# Sheet1_35131-35133.net
KiCad netlist of a schematic drawn in Altium Designer
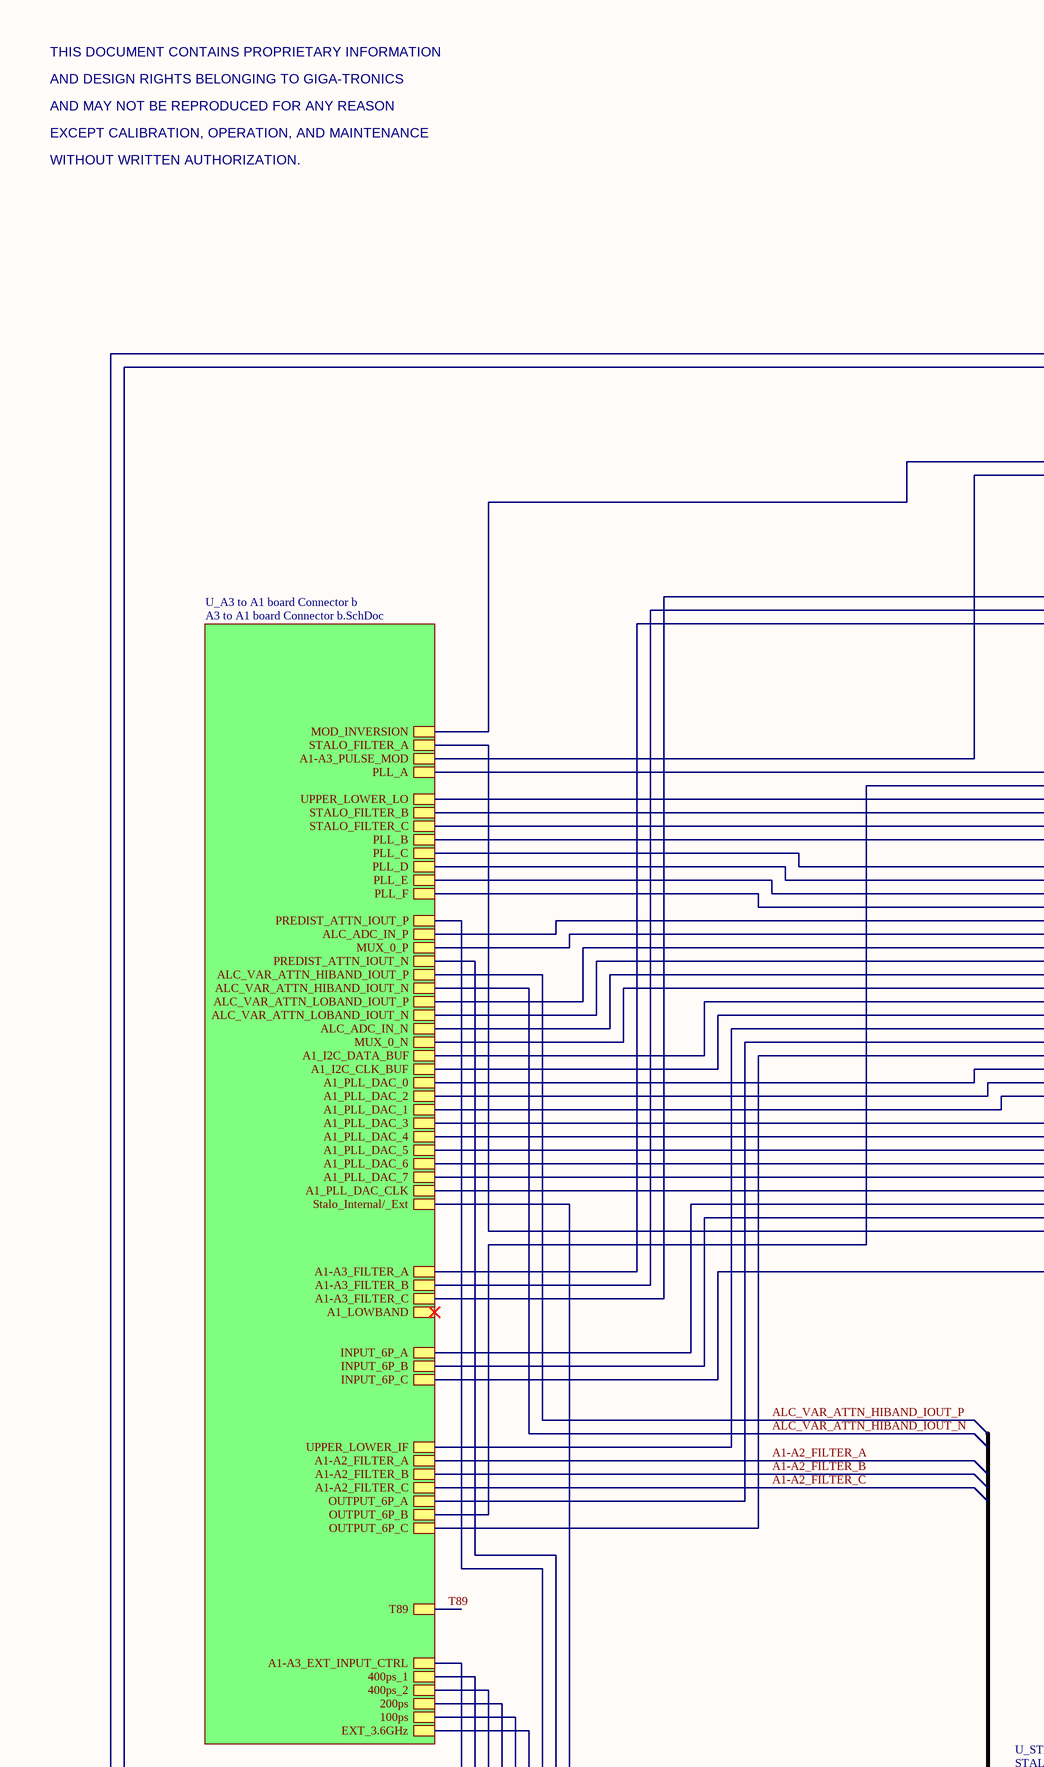
[diagram p0: Sheet1_35131-35133.SchDoc, top left]
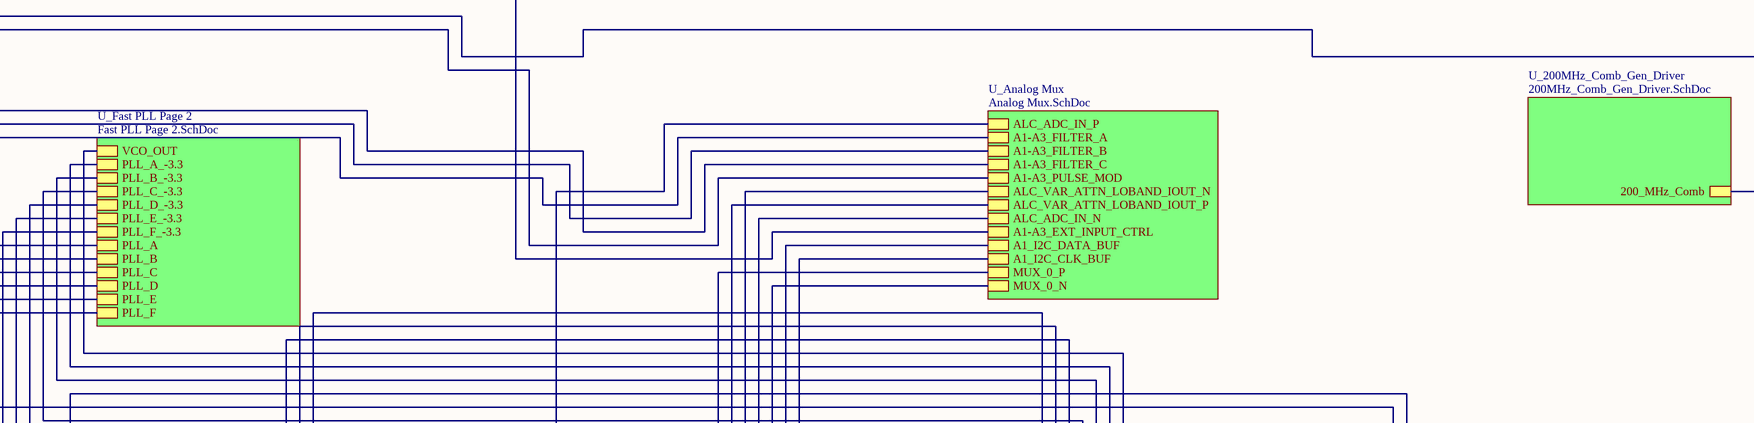
[diagram p1: Sheet1_35131-35133.SchDoc, top middle]
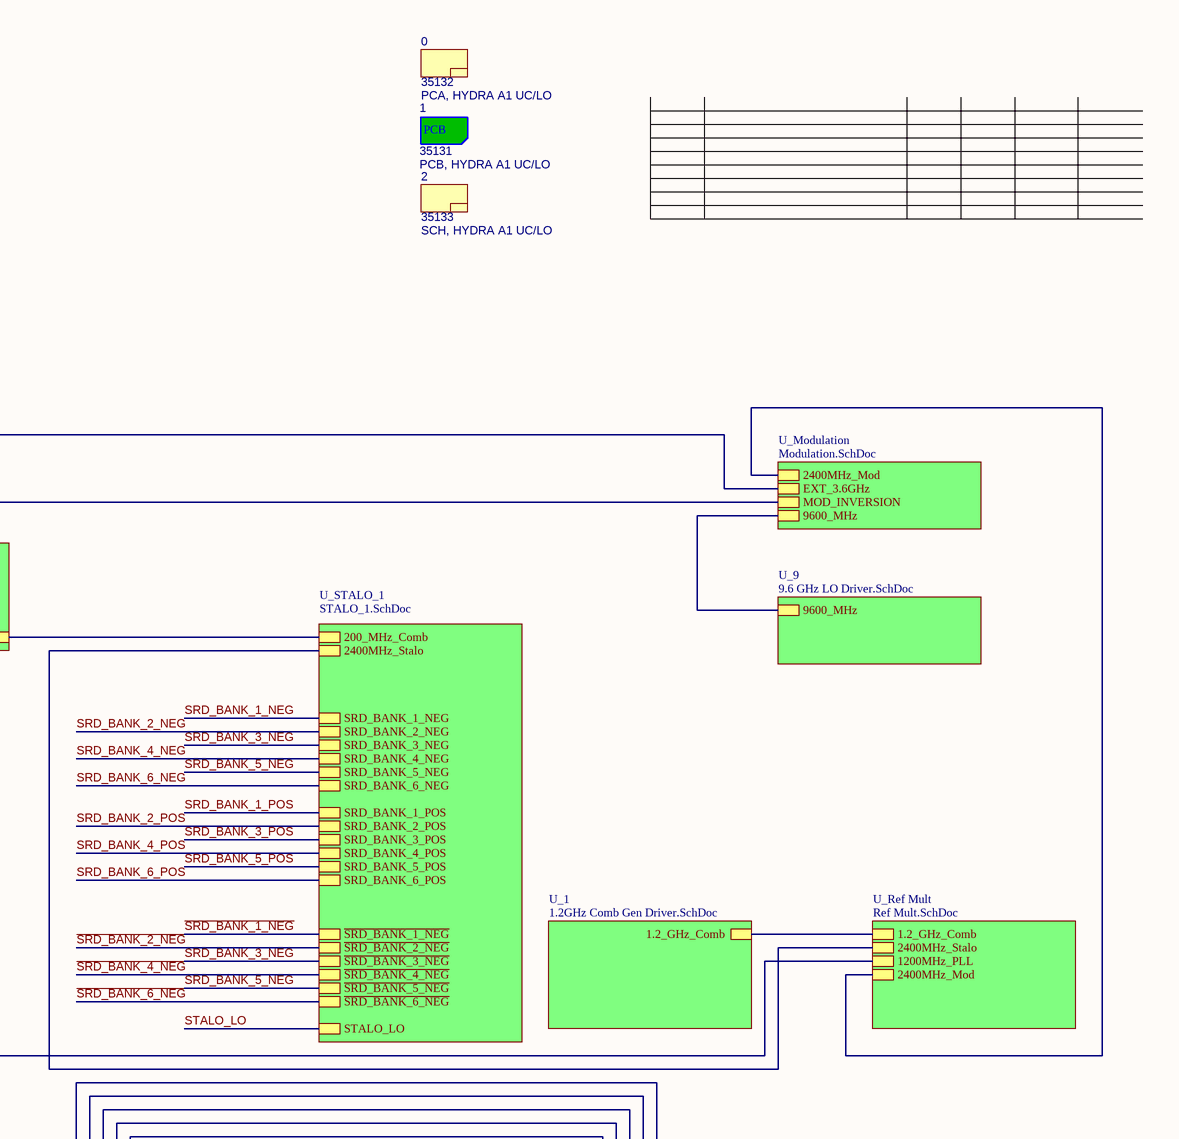
[diagram p2: Sheet1_35131-35133.SchDoc, top right]
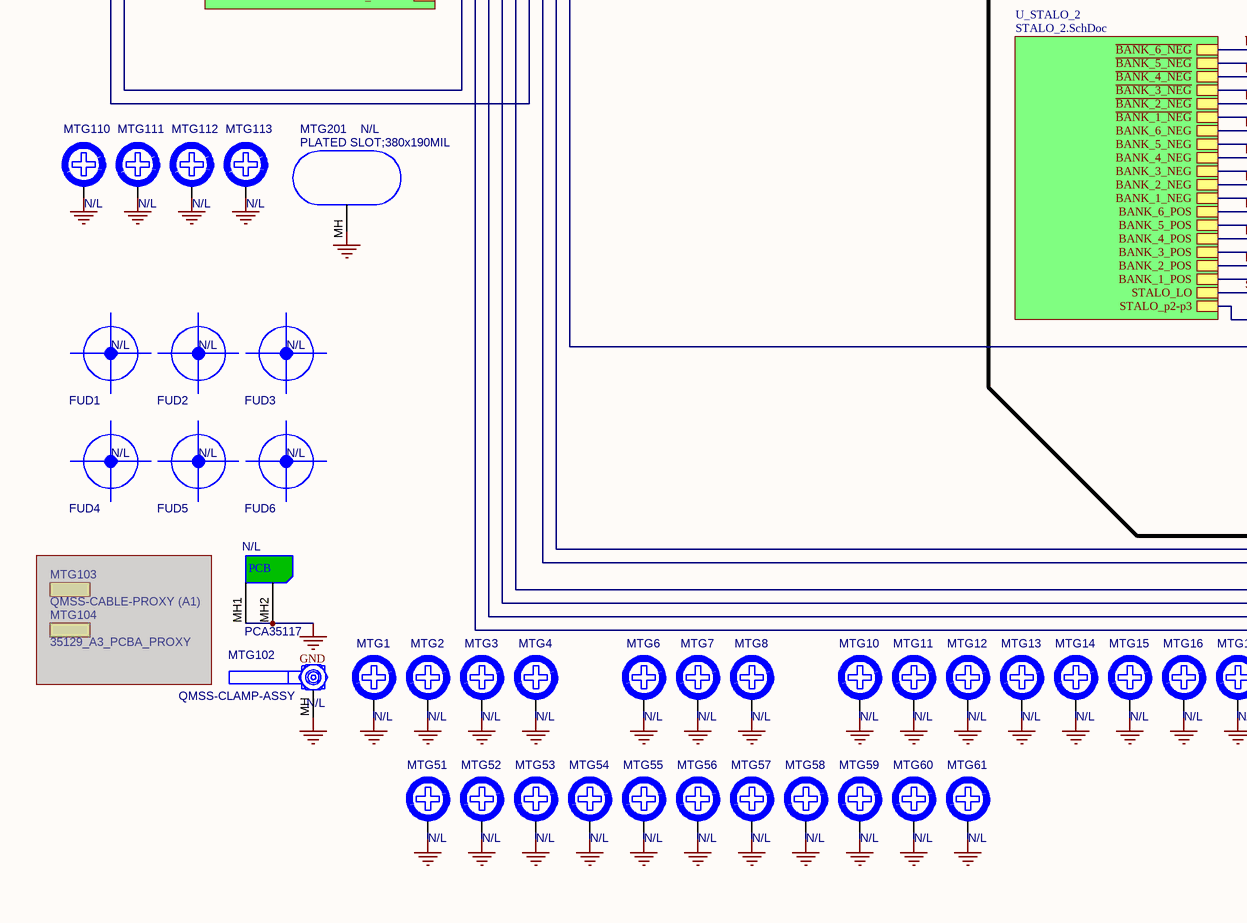
[diagram p3: Sheet1_35131-35133.SchDoc, bottom left]
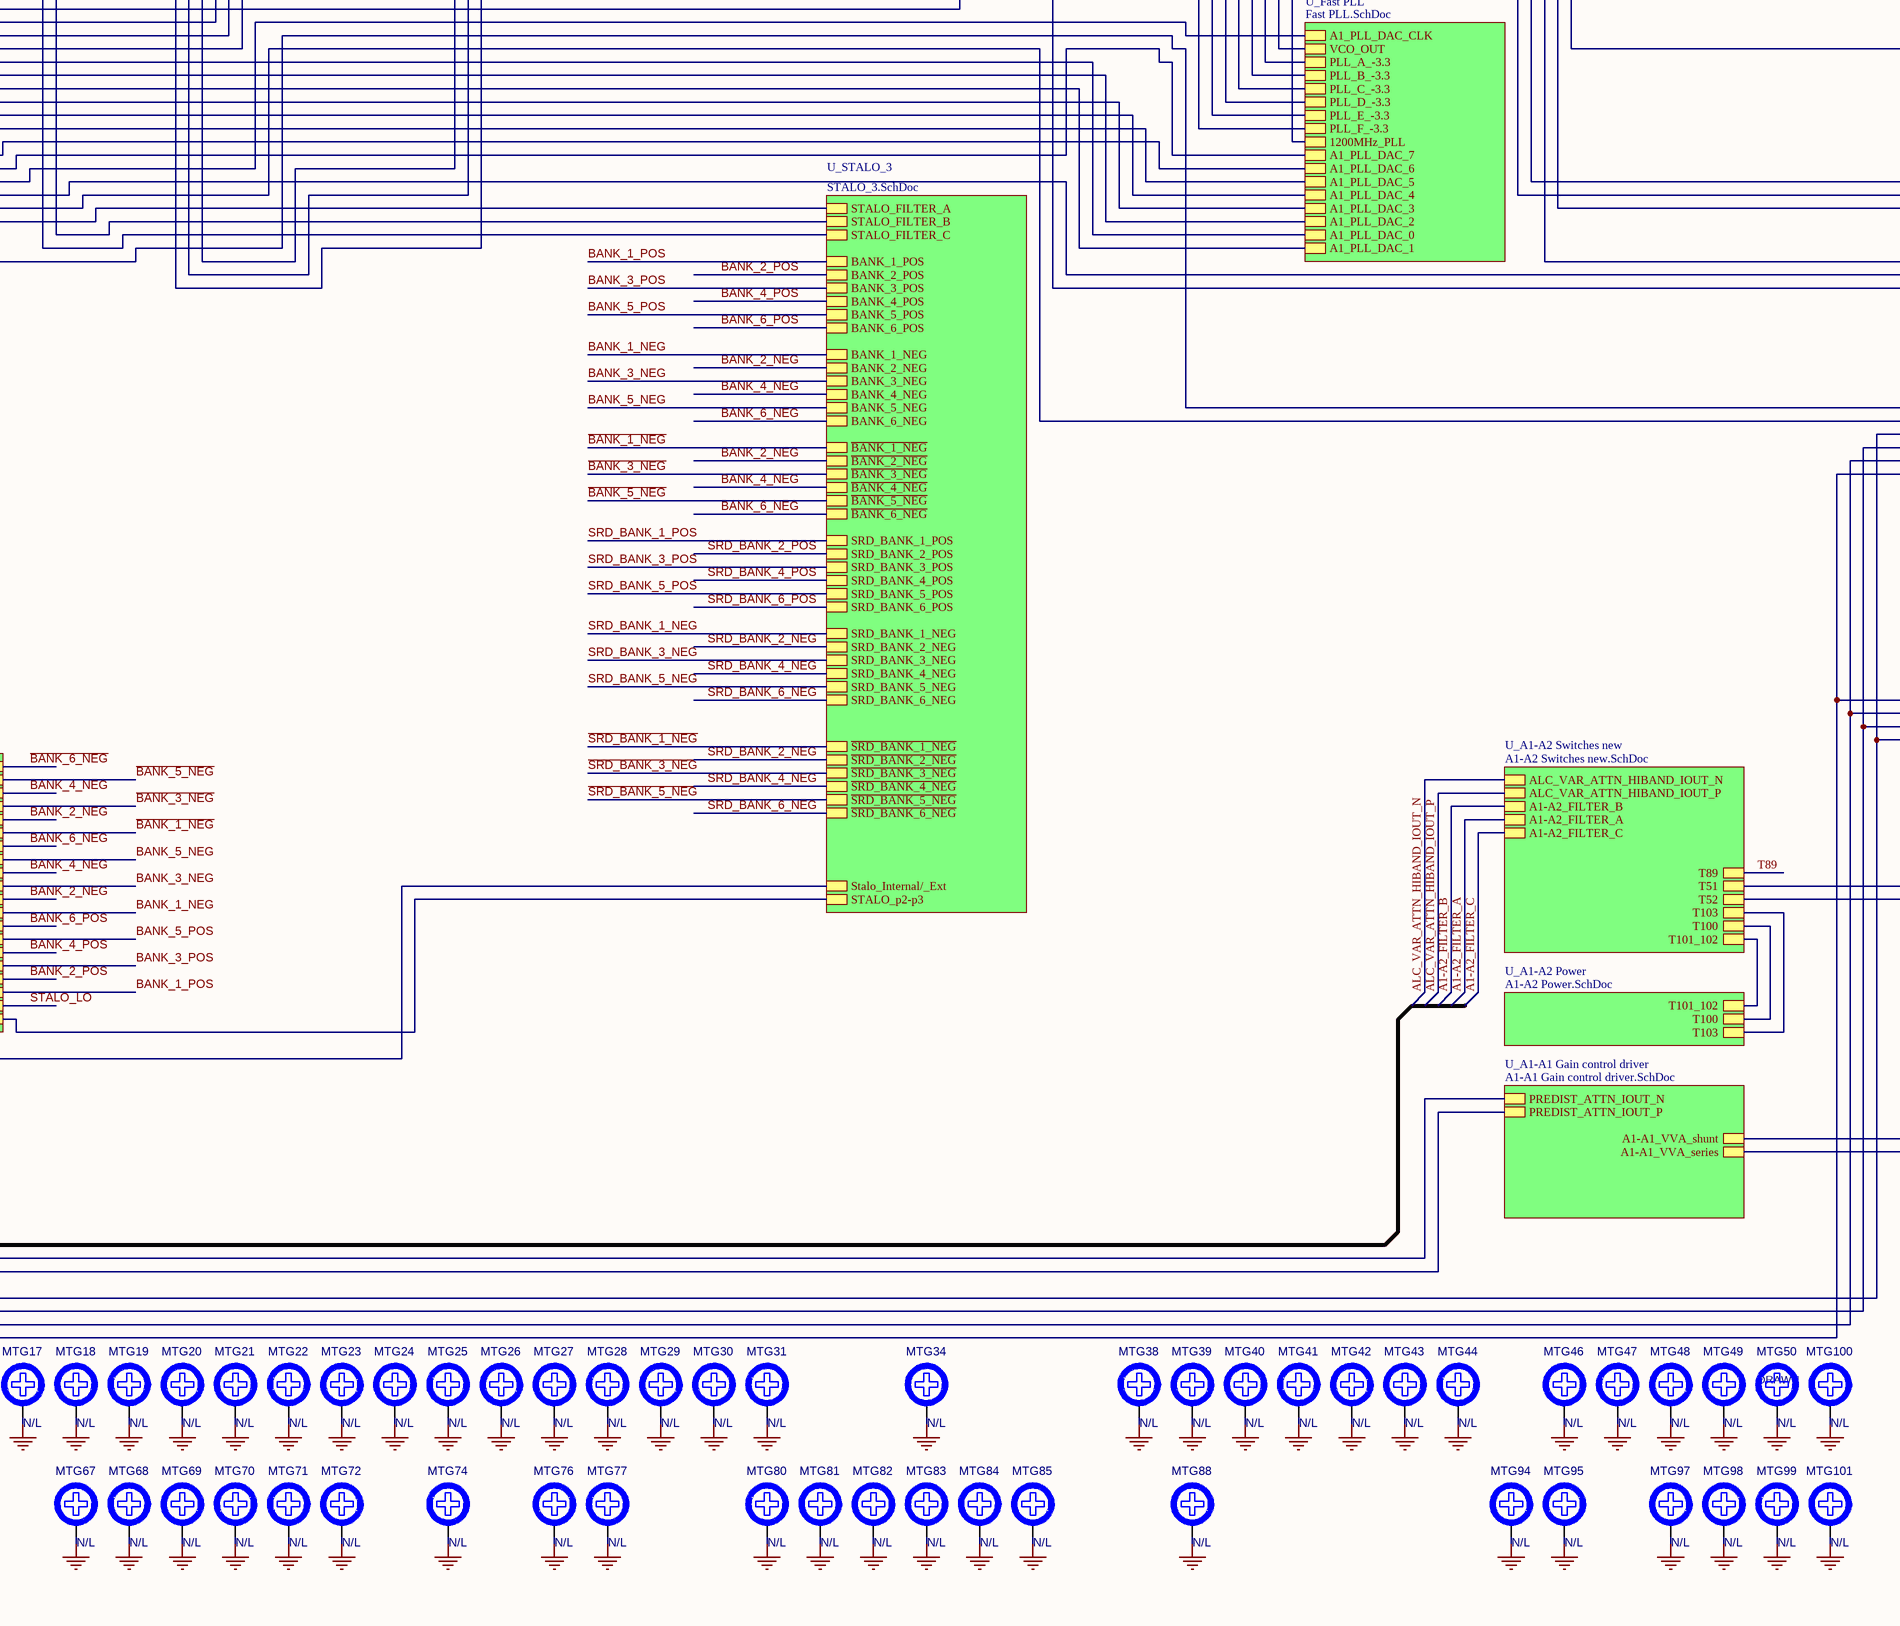
[diagram p4: Sheet1_35131-35133.SchDoc, bottom middle]
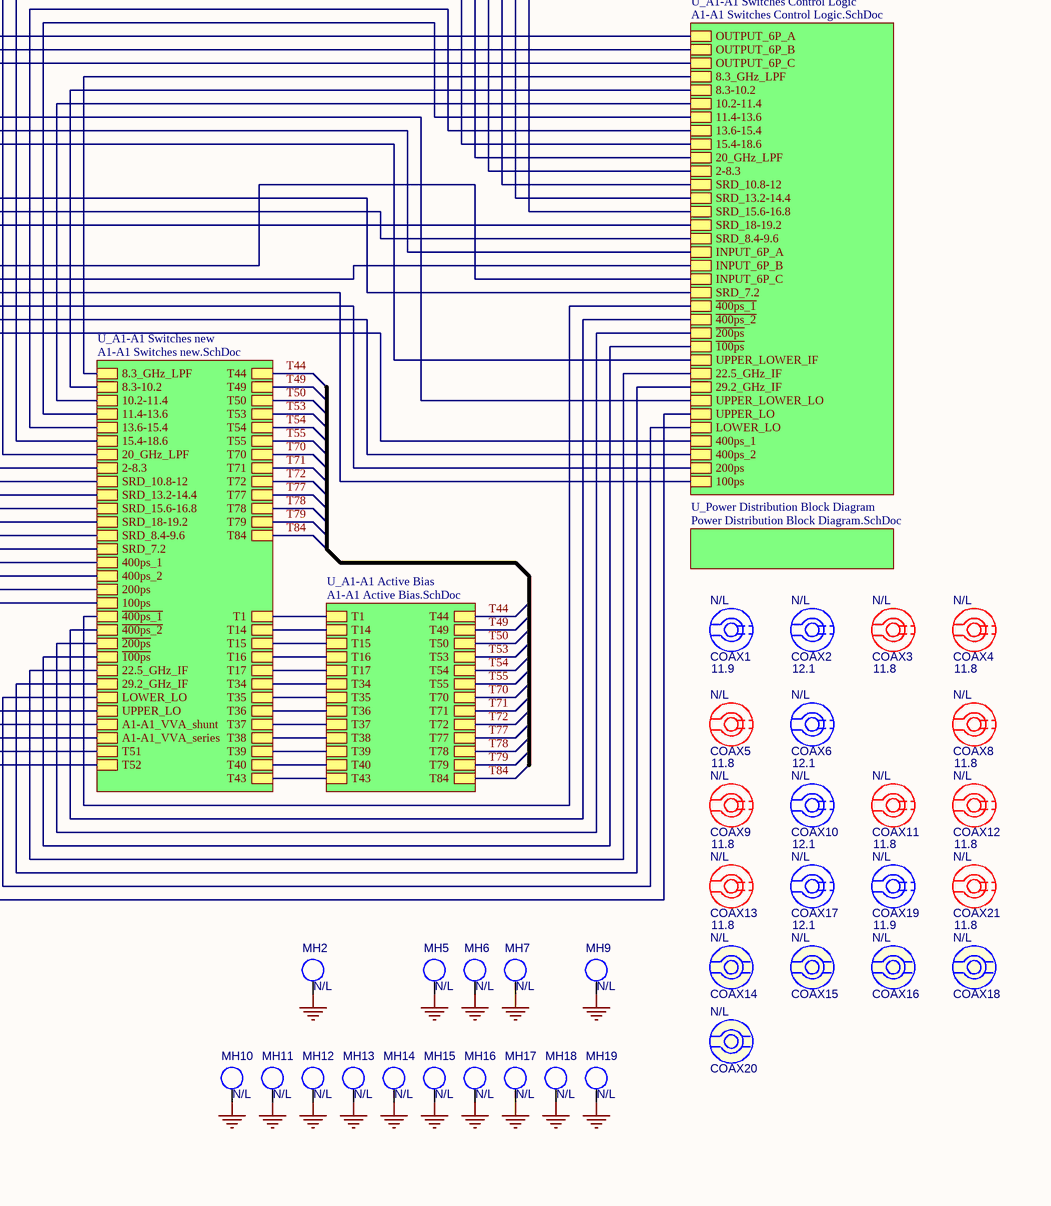
[diagram p5: Sheet1_35131-35133.SchDoc, bottom right]

(export (version "E")
  (design (tool "Eeschema 10.0.6"))
  (components
    (comp (ref "0")
      (value "PCA, HYDRA A1 UC/LO")
      (fields (field (name "ITEM_NUMBER") "35132") (field (name "Comment") "35132"))
      (libsource (lib "35133") (part "35132"))
    )
    (comp (ref "1")
      (value "PCB, HYDRA A1 UC/LO")
      (fields
        (field (name "ITEM_NUMBER") "35131")
        (field (name "Comment") "35131")
        (field (name "APPROVED") "MH")
      )
      (libsource (lib "35133") (part "35131"))
    )
    (comp (ref "2")
      (value "SCH, HYDRA A1 UC/LO")
      (fields (field (name "ITEM_NUMBER") "35133") (field (name "Comment") "35133"))
      (libsource (lib "35133") (part "35133"))
    )
    (comp (ref "COAX1")
      (value "Coax Bot-Mid4")
      (footprint "Coax_Bot-Mid4")
      (fields (field (name "NOLOAD") "N/L"))
      (libsource (lib "Giga-tronics") (part "Coax Bot-Mid4"))
    )
    (comp (ref "COAX2")
      (value "Coax Bot-Mid4")
      (footprint "Coax_Bot-Mid4")
      (fields (field (name "NOLOAD") "N/L"))
      (libsource (lib "Giga-tronics") (part "Coax Bot-Mid4"))
    )
    (comp (ref "COAX3")
      (value "Coax Top-Mid3")
      (footprint "Coax_Top-Mid3")
      (fields (field (name "NOLOAD") "N/L"))
      (libsource (lib "Giga-tronics") (part "Coax Top-Mid3"))
    )
    (comp (ref "COAX4")
      (value "Coax Top-Mid3")
      (footprint "Coax_Top-Mid3")
      (fields (field (name "NOLOAD") "N/L"))
      (libsource (lib "Giga-tronics") (part "Coax Top-Mid3"))
    )
    (comp (ref "COAX5")
      (value "Coax Top-Mid3")
      (footprint "Coax_Top-Mid3")
      (fields (field (name "NOLOAD") "N/L"))
      (libsource (lib "Giga-tronics") (part "Coax Top-Mid3"))
    )
    (comp (ref "COAX6")
      (value "Coax Bot-Mid4")
      (footprint "Coax_Bot-Mid4")
      (fields (field (name "NOLOAD") "N/L"))
      (libsource (lib "Giga-tronics") (part "Coax Bot-Mid4"))
    )
    (comp (ref "COAX8")
      (value "Coax Top-Mid3")
      (footprint "Coax_Top-Mid3")
      (fields (field (name "NOLOAD") "N/L"))
      (libsource (lib "Giga-tronics") (part "Coax Top-Mid3"))
    )
    (comp (ref "COAX9")
      (value "Coax Top-Mid3")
      (footprint "Coax_Top-Mid3")
      (fields (field (name "NOLOAD") "N/L"))
      (libsource (lib "Giga-tronics") (part "Coax Top-Mid3"))
    )
    (comp (ref "COAX10")
      (value "Coax Bot-Mid4")
      (footprint "Coax_Bot-Mid4")
      (fields (field (name "NOLOAD") "N/L"))
      (libsource (lib "Giga-tronics") (part "Coax Bot-Mid4"))
    )
    (comp (ref "COAX11")
      (value "Coax Top-Mid3")
      (footprint "Coax_Top-Mid3")
      (fields (field (name "NOLOAD") "N/L"))
      (libsource (lib "Giga-tronics") (part "Coax Top-Mid3"))
    )
    (comp (ref "COAX12")
      (value "Coax Top-Mid3")
      (footprint "Coax_Top-Mid3")
      (fields (field (name "NOLOAD") "N/L"))
      (libsource (lib "Giga-tronics") (part "Coax Top-Mid3"))
    )
    (comp (ref "COAX13")
      (value "Coax Top-Mid3")
      (footprint "Coax_Top-Mid3")
      (fields (field (name "NOLOAD") "N/L"))
      (libsource (lib "Giga-tronics") (part "Coax Top-Mid3"))
    )
    (comp (ref "COAX14")
      (value "Coax Top-Bot")
      (footprint "Coax_Top-Bot")
      (fields (field (name "NOLOAD") "N/L"))
      (libsource (lib "Giga-tronics") (part "Coax Top-Bot"))
    )
    (comp (ref "COAX15")
      (value "Coax Top-Bot")
      (footprint "Coax_Top-Bot")
      (fields (field (name "NOLOAD") "N/L"))
      (libsource (lib "Giga-tronics") (part "Coax Top-Bot"))
    )
    (comp (ref "COAX16")
      (value "Coax Top-Bot")
      (footprint "Coax_Top-Bot")
      (fields (field (name "NOLOAD") "N/L"))
      (libsource (lib "Giga-tronics") (part "Coax Top-Bot"))
    )
    (comp (ref "COAX17")
      (value "Coax Bot-Mid4")
      (footprint "Coax_Bot-Mid4")
      (fields (field (name "NOLOAD") "N/L"))
      (libsource (lib "Giga-tronics") (part "Coax Bot-Mid4"))
    )
    (comp (ref "COAX18")
      (value "Coax Top-Bot")
      (footprint "Coax_Top-Bot")
      (fields (field (name "NOLOAD") "N/L"))
      (libsource (lib "Giga-tronics") (part "Coax Top-Bot"))
    )
    (comp (ref "COAX19")
      (value "Coax Bot-Mid4")
      (footprint "Coax_Bot-Mid4")
      (fields (field (name "NOLOAD") "N/L"))
      (libsource (lib "Giga-tronics") (part "Coax Bot-Mid4"))
    )
    (comp (ref "COAX20")
      (value "Coax Top-Bot")
      (footprint "Coax_Top-Bot")
      (fields (field (name "NOLOAD") "N/L"))
      (libsource (lib "Giga-tronics") (part "Coax Top-Bot"))
    )
    (comp (ref "COAX21")
      (value "Coax Top-Mid3")
      (footprint "Coax_Top-Mid3")
      (fields (field (name "NOLOAD") "N/L"))
      (libsource (lib "Giga-tronics") (part "Coax Top-Mid3"))
    )
    (comp (ref "FUD1")
      (value "FIDUCIAL_GLOBAL")
      (footprint "FIDUCIAL_GLOBAL")
      (fields (field (name "NOLOAD") "N/L"))
      (libsource (lib "Giga-tronics") (part "FIDUCIAL_GLOBAL"))
    )
    (comp (ref "FUD2")
      (value "FIDUCIAL_GLOBAL")
      (footprint "FIDUCIAL_GLOBAL")
      (fields (field (name "NOLOAD") "N/L"))
      (libsource (lib "Giga-tronics") (part "FIDUCIAL_GLOBAL"))
    )
    (comp (ref "FUD3")
      (value "FIDUCIAL_GLOBAL")
      (footprint "FIDUCIAL_GLOBAL")
      (fields (field (name "NOLOAD") "N/L"))
      (libsource (lib "Giga-tronics") (part "FIDUCIAL_GLOBAL"))
    )
    (comp (ref "FUD4")
      (value "FIDUCIAL_GLOBAL")
      (footprint "FIDUCIAL_GLOBAL")
      (fields (field (name "NOLOAD") "N/L"))
      (libsource (lib "Giga-tronics") (part "FIDUCIAL_GLOBAL"))
    )
    (comp (ref "FUD5")
      (value "FIDUCIAL_GLOBAL")
      (footprint "FIDUCIAL_GLOBAL")
      (fields (field (name "NOLOAD") "N/L"))
      (libsource (lib "Giga-tronics") (part "FIDUCIAL_GLOBAL"))
    )
    (comp (ref "FUD6")
      (value "FIDUCIAL_GLOBAL")
      (footprint "FIDUCIAL_GLOBAL")
      (fields (field (name "NOLOAD") "N/L"))
      (libsource (lib "Giga-tronics") (part "FIDUCIAL_GLOBAL"))
    )
    (comp (ref "MH2")
      (value "N/L")
      (footprint "MHP-250X116")
      (description "MHP-250X116")
      (fields (field (name "NOLOAD") "N/L"))
      (libsource (lib "Giga-tronics") (part "MHP-250X116"))
    )
    (comp (ref "MH5")
      (value "N/L")
      (footprint "MHP-250X116")
      (description "MHP-250X116")
      (fields (field (name "NOLOAD") "N/L"))
      (libsource (lib "Giga-tronics") (part "MHP-250X116"))
    )
    (comp (ref "MH6")
      (value "N/L")
      (footprint "MHP-250X116")
      (description "MHP-250X116")
      (fields (field (name "NOLOAD") "N/L"))
      (libsource (lib "Giga-tronics") (part "MHP-250X116"))
    )
    (comp (ref "MH7")
      (value "N/L")
      (footprint "MHP-250X116")
      (description "MHP-250X116")
      (fields (field (name "NOLOAD") "N/L"))
      (libsource (lib "Giga-tronics") (part "MHP-250X116"))
    )
    (comp (ref "MH9")
      (value "N/L")
      (footprint "MHP-250X116")
      (description "MHP-250X116")
      (fields (field (name "NOLOAD") "N/L"))
      (libsource (lib "Giga-tronics") (part "MHP-250X116"))
    )
    (comp (ref "MH10")
      (value "N/L")
      (footprint "MHP-250X116")
      (description "MHP-250X116")
      (fields (field (name "NOLOAD") "N/L"))
      (libsource (lib "Giga-tronics") (part "MHP-250X116"))
    )
    (comp (ref "MH11")
      (value "N/L")
      (footprint "MHP-250X116")
      (description "MHP-250X116")
      (fields (field (name "NOLOAD") "N/L"))
      (libsource (lib "Giga-tronics") (part "MHP-250X116"))
    )
    (comp (ref "MH12")
      (value "N/L")
      (footprint "MHP-250X116")
      (description "MHP-250X116")
      (fields (field (name "NOLOAD") "N/L"))
      (libsource (lib "Giga-tronics") (part "MHP-250X116"))
    )
    (comp (ref "MH13")
      (value "N/L")
      (footprint "MHP-250X116")
      (description "MHP-250X116")
      (fields (field (name "NOLOAD") "N/L"))
      (libsource (lib "Giga-tronics") (part "MHP-250X116"))
    )
    (comp (ref "MH14")
      (value "N/L")
      (footprint "MHP-250X116")
      (description "MHP-250X116")
      (fields (field (name "NOLOAD") "N/L"))
      (libsource (lib "Giga-tronics") (part "MHP-250X116"))
    )
    (comp (ref "MH15")
      (value "N/L")
      (footprint "MHP-250X116")
      (description "MHP-250X116")
      (fields (field (name "NOLOAD") "N/L"))
      (libsource (lib "Giga-tronics") (part "MHP-250X116"))
    )
    (comp (ref "MH16")
      (value "N/L")
      (footprint "MHP-250X116")
      (description "MHP-250X116")
      (fields (field (name "NOLOAD") "N/L"))
      (libsource (lib "Giga-tronics") (part "MHP-250X116"))
    )
    (comp (ref "MH17")
      (value "N/L")
      (footprint "MHP-250X116")
      (description "MHP-250X116")
      (fields (field (name "NOLOAD") "N/L"))
      (libsource (lib "Giga-tronics") (part "MHP-250X116"))
    )
    (comp (ref "MH18")
      (value "N/L")
      (footprint "MHP-250X116")
      (description "MHP-250X116")
      (fields (field (name "NOLOAD") "N/L"))
      (libsource (lib "Giga-tronics") (part "MHP-250X116"))
    )
    (comp (ref "MH19")
      (value "N/L")
      (footprint "MHP-250X116")
      (description "MHP-250X116")
      (fields (field (name "NOLOAD") "N/L"))
      (libsource (lib "Giga-tronics") (part "MHP-250X116"))
    )
    (comp (ref "MTG1")
      (value "~")
      (footprint "MHP200X92")
      (description "MHP200X92")
      (fields (field (name "NOLOAD") "N/L"))
      (libsource (lib "Giga-tronics") (part "MHP200X92"))
    )
    (comp (ref "MTG2")
      (value "~")
      (footprint "MHP200X92")
      (description "MHP200X92")
      (fields (field (name "NOLOAD") "N/L"))
      (libsource (lib "Giga-tronics") (part "MHP200X92"))
    )
    (comp (ref "MTG3")
      (value "~")
      (footprint "MHP200X92")
      (description "MHP200X92")
      (fields (field (name "NOLOAD") "N/L"))
      (libsource (lib "Giga-tronics") (part "MHP200X92"))
    )
    (comp (ref "MTG4")
      (value "~")
      (footprint "MHP200X92")
      (description "MHP200X92")
      (fields (field (name "NOLOAD") "N/L"))
      (libsource (lib "Giga-tronics") (part "MHP200X92"))
    )
    (comp (ref "MTG6")
      (value "~")
      (footprint "MHP200X92")
      (description "MHP200X92")
      (fields (field (name "NOLOAD") "N/L"))
      (libsource (lib "Giga-tronics") (part "MHP200X92"))
    )
    (comp (ref "MTG7")
      (value "~")
      (footprint "MHP200X92")
      (description "MHP200X92")
      (fields (field (name "NOLOAD") "N/L"))
      (libsource (lib "Giga-tronics") (part "MHP200X92"))
    )
    (comp (ref "MTG8")
      (value "~")
      (footprint "MHP200X92")
      (description "MHP200X92")
      (fields (field (name "NOLOAD") "N/L"))
      (libsource (lib "Giga-tronics") (part "MHP200X92"))
    )
    (comp (ref "MTG10")
      (value "~")
      (footprint "MHP200X92")
      (description "MHP200X92")
      (fields (field (name "NOLOAD") "N/L"))
      (libsource (lib "Giga-tronics") (part "MHP200X92"))
    )
    (comp (ref "MTG11")
      (value "~")
      (footprint "MHP200X92")
      (description "MHP200X92")
      (fields (field (name "NOLOAD") "N/L"))
      (libsource (lib "Giga-tronics") (part "MHP200X92"))
    )
    (comp (ref "MTG12")
      (value "~")
      (footprint "MHP200X92")
      (description "MHP200X92")
      (fields (field (name "NOLOAD") "N/L"))
      (libsource (lib "Giga-tronics") (part "MHP200X92"))
    )
    (comp (ref "MTG13")
      (value "~")
      (footprint "MHP200X92")
      (description "MHP200X92")
      (fields (field (name "NOLOAD") "N/L"))
      (libsource (lib "Giga-tronics") (part "MHP200X92"))
    )
    (comp (ref "MTG14")
      (value "~")
      (footprint "MHP200X92")
      (description "MHP200X92")
      (fields (field (name "NOLOAD") "N/L"))
      (libsource (lib "Giga-tronics") (part "MHP200X92"))
    )
    (comp (ref "MTG15")
      (value "~")
      (footprint "MHP200X92")
      (description "MHP200X92")
      (fields (field (name "NOLOAD") "N/L"))
      (libsource (lib "Giga-tronics") (part "MHP200X92"))
    )
    (comp (ref "MTG16")
      (value "~")
      (footprint "MHP200X92")
      (description "MHP200X92")
      (fields (field (name "NOLOAD") "N/L"))
      (libsource (lib "Giga-tronics") (part "MHP200X92"))
    )
    (comp (ref "MTG17")
      (value "~")
      (footprint "MHP200X92")
      (description "MHP200X92")
      (fields (field (name "NOLOAD") "N/L"))
      (libsource (lib "Giga-tronics") (part "MHP200X92"))
    )
    (comp (ref "MTG18")
      (value "~")
      (footprint "MHP200X92")
      (description "MHP200X92")
      (fields (field (name "NOLOAD") "N/L"))
      (libsource (lib "Giga-tronics") (part "MHP200X92"))
    )
    (comp (ref "MTG19")
      (value "~")
      (footprint "MHP200X92")
      (description "MHP200X92")
      (fields (field (name "NOLOAD") "N/L"))
      (libsource (lib "Giga-tronics") (part "MHP200X92"))
    )
    (comp (ref "MTG20")
      (value "~")
      (footprint "MHP200X92")
      (description "MHP200X92")
      (fields (field (name "NOLOAD") "N/L"))
      (libsource (lib "Giga-tronics") (part "MHP200X92"))
    )
    (comp (ref "MTG21")
      (value "~")
      (footprint "MHP200X92")
      (description "MHP200X92")
      (fields (field (name "NOLOAD") "N/L"))
      (libsource (lib "Giga-tronics") (part "MHP200X92"))
    )
    (comp (ref "MTG22")
      (value "~")
      (footprint "MHP200X92")
      (description "MHP200X92")
      (fields (field (name "NOLOAD") "N/L"))
      (libsource (lib "Giga-tronics") (part "MHP200X92"))
    )
    (comp (ref "MTG23")
      (value "~")
      (footprint "MHP200X92")
      (description "MHP200X92")
      (fields (field (name "NOLOAD") "N/L"))
      (libsource (lib "Giga-tronics") (part "MHP200X92"))
    )
    (comp (ref "MTG24")
      (value "~")
      (footprint "MHP200X92")
      (description "MHP200X92")
      (fields (field (name "NOLOAD") "N/L"))
      (libsource (lib "Giga-tronics") (part "MHP200X92"))
    )
    (comp (ref "MTG25")
      (value "~")
      (footprint "MHP200X92")
      (description "MHP200X92")
      (fields (field (name "NOLOAD") "N/L"))
      (libsource (lib "Giga-tronics") (part "MHP200X92"))
    )
    (comp (ref "MTG26")
      (value "~")
      (footprint "MHP200X92")
      (description "MHP200X92")
      (fields (field (name "NOLOAD") "N/L"))
      (libsource (lib "Giga-tronics") (part "MHP200X92"))
    )
    (comp (ref "MTG27")
      (value "~")
      (footprint "MHP200X92")
      (description "MHP200X92")
      (fields (field (name "NOLOAD") "N/L"))
      (libsource (lib "Giga-tronics") (part "MHP200X92"))
    )
    (comp (ref "MTG28")
      (value "~")
      (footprint "MHP200X92")
      (description "MHP200X92")
      (fields (field (name "NOLOAD") "N/L"))
      (libsource (lib "Giga-tronics") (part "MHP200X92"))
    )
    (comp (ref "MTG29")
      (value "~")
      (footprint "MHP200X92")
      (description "MHP200X92")
      (fields (field (name "NOLOAD") "N/L"))
      (libsource (lib "Giga-tronics") (part "MHP200X92"))
    )
    (comp (ref "MTG30")
      (value "~")
      (footprint "MHP200X92")
      (description "MHP200X92")
      (fields (field (name "NOLOAD") "N/L"))
      (libsource (lib "Giga-tronics") (part "MHP200X92"))
    )
    (comp (ref "MTG31")
      (value "~")
      (footprint "MHP200X92")
      (description "MHP200X92")
      (fields (field (name "NOLOAD") "N/L"))
      (libsource (lib "Giga-tronics") (part "MHP200X92"))
    )
    (comp (ref "MTG34")
      (value "~")
      (footprint "MHP200X92")
      (description "MHP200X92")
      (fields (field (name "NOLOAD") "N/L"))
      (libsource (lib "Giga-tronics") (part "MHP200X92"))
    )
    (comp (ref "MTG38")
      (value "~")
      (footprint "MHP200X92")
      (description "MHP200X92")
      (fields (field (name "NOLOAD") "N/L"))
      (libsource (lib "Giga-tronics") (part "MHP200X92"))
    )
    (comp (ref "MTG39")
      (value "~")
      (footprint "MHP200X92")
      (description "MHP200X92")
      (fields (field (name "NOLOAD") "N/L"))
      (libsource (lib "Giga-tronics") (part "MHP200X92"))
    )
    (comp (ref "MTG40")
      (value "~")
      (footprint "MHP200X92")
      (description "MHP200X92")
      (fields (field (name "NOLOAD") "N/L"))
      (libsource (lib "Giga-tronics") (part "MHP200X92"))
    )
    (comp (ref "MTG41")
      (value "~")
      (footprint "MHP200X92")
      (description "MHP200X92")
      (fields (field (name "NOLOAD") "N/L"))
      (libsource (lib "Giga-tronics") (part "MHP200X92"))
    )
    (comp (ref "MTG42")
      (value "~")
      (footprint "MHP200X92")
      (description "MHP200X92")
      (fields (field (name "NOLOAD") "N/L"))
      (libsource (lib "Giga-tronics") (part "MHP200X92"))
    )
    (comp (ref "MTG43")
      (value "~")
      (footprint "MHP200X92")
      (description "MHP200X92")
      (fields (field (name "NOLOAD") "N/L"))
      (libsource (lib "Giga-tronics") (part "MHP200X92"))
    )
    (comp (ref "MTG44")
      (value "~")
      (footprint "MHP200X92")
      (description "MHP200X92")
      (fields (field (name "NOLOAD") "N/L"))
      (libsource (lib "Giga-tronics") (part "MHP200X92"))
    )
    (comp (ref "MTG46")
      (value "~")
      (footprint "MHP200X92")
      (description "MHP200X92")
      (fields (field (name "NOLOAD") "N/L"))
      (libsource (lib "Giga-tronics") (part "MHP200X92"))
    )
    (comp (ref "MTG47")
      (value "~")
      (footprint "MHP200X92")
      (description "MHP200X92")
      (fields (field (name "NOLOAD") "N/L"))
      (libsource (lib "Giga-tronics") (part "MHP200X92"))
    )
    (comp (ref "MTG48")
      (value "~")
      (footprint "MHP200X92")
      (description "MHP200X92")
      (fields (field (name "NOLOAD") "N/L"))
      (libsource (lib "Giga-tronics") (part "MHP200X92"))
    )
    (comp (ref "MTG49")
      (value "~")
      (footprint "MHP200X92")
      (description "MHP200X92")
      (fields (field (name "NOLOAD") "N/L"))
      (libsource (lib "Giga-tronics") (part "MHP200X92"))
    )
    (comp (ref "MTG50")
      (value "~")
      (footprint "MHP200X92")
      (description "MHP200X92")
      (fields (field (name "NOLOAD") "N/L"))
      (libsource (lib "Giga-tronics") (part "MHP200X92"))
    )
    (comp (ref "MTG51")
      (value "~")
      (footprint "MHP200X92")
      (description "MHP200X92")
      (fields (field (name "NOLOAD") "N/L"))
      (libsource (lib "Giga-tronics") (part "MHP200X92"))
    )
    (comp (ref "MTG52")
      (value "~")
      (footprint "MHP200X92")
      (description "MHP200X92")
      (fields (field (name "NOLOAD") "N/L"))
      (libsource (lib "Giga-tronics") (part "MHP200X92"))
    )
    (comp (ref "MTG53")
      (value "~")
      (footprint "MHP200X92")
      (description "MHP200X92")
      (fields (field (name "NOLOAD") "N/L"))
      (libsource (lib "Giga-tronics") (part "MHP200X92"))
    )
    (comp (ref "MTG54")
      (value "~")
      (footprint "MHP200X92")
      (description "MHP200X92")
      (fields (field (name "NOLOAD") "N/L"))
      (libsource (lib "Giga-tronics") (part "MHP200X92"))
    )
    (comp (ref "MTG55")
      (value "~")
      (footprint "MHP200X92")
      (description "MHP200X92")
      (fields (field (name "NOLOAD") "N/L"))
      (libsource (lib "Giga-tronics") (part "MHP200X92"))
    )
    (comp (ref "MTG56")
      (value "~")
      (footprint "MHP200X92")
      (description "MHP200X92")
      (fields (field (name "NOLOAD") "N/L"))
      (libsource (lib "Giga-tronics") (part "MHP200X92"))
    )
    (comp (ref "MTG57")
      (value "~")
      (footprint "MHP200X92")
      (description "MHP200X92")
      (fields (field (name "NOLOAD") "N/L"))
      (libsource (lib "Giga-tronics") (part "MHP200X92"))
    )
    (comp (ref "MTG58")
      (value "~")
      (footprint "MHP200X92")
      (description "MHP200X92")
      (fields (field (name "NOLOAD") "N/L"))
      (libsource (lib "Giga-tronics") (part "MHP200X92"))
    )
    (comp (ref "MTG59")
      (value "~")
      (footprint "MHP200X92")
      (description "MHP200X92")
      (fields (field (name "NOLOAD") "N/L"))
      (libsource (lib "Giga-tronics") (part "MHP200X92"))
    )
    (comp (ref "MTG60")
      (value "~")
      (footprint "MHP200X92")
      (description "MHP200X92")
      (fields (field (name "NOLOAD") "N/L"))
      (libsource (lib "Giga-tronics") (part "MHP200X92"))
    )
    (comp (ref "MTG61")
      (value "~")
      (footprint "MHP200X92")
      (description "MHP200X92")
      (fields (field (name "NOLOAD") "N/L"))
      (libsource (lib "Giga-tronics") (part "MHP200X92"))
    )
    (comp (ref "MTG67")
      (value "~")
      (footprint "MHP200X92")
      (description "MHP200X92")
      (fields (field (name "NOLOAD") "N/L"))
      (libsource (lib "Giga-tronics") (part "MHP200X92"))
    )
    (comp (ref "MTG68")
      (value "~")
      (footprint "MHP200X92")
      (description "MHP200X92")
      (fields (field (name "NOLOAD") "N/L"))
      (libsource (lib "Giga-tronics") (part "MHP200X92"))
    )
    (comp (ref "MTG69")
      (value "~")
      (footprint "MHP200X92")
      (description "MHP200X92")
      (fields (field (name "NOLOAD") "N/L"))
      (libsource (lib "Giga-tronics") (part "MHP200X92"))
    )
    (comp (ref "MTG70")
      (value "~")
      (footprint "MHP200X92")
      (description "MHP200X92")
      (fields (field (name "NOLOAD") "N/L"))
      (libsource (lib "Giga-tronics") (part "MHP200X92"))
    )
    (comp (ref "MTG71")
      (value "~")
      (footprint "MHP200X92")
      (description "MHP200X92")
      (fields (field (name "NOLOAD") "N/L"))
      (libsource (lib "Giga-tronics") (part "MHP200X92"))
    )
    (comp (ref "MTG72")
      (value "~")
      (footprint "MHP200X92")
      (description "MHP200X92")
      (fields (field (name "NOLOAD") "N/L"))
      (libsource (lib "Giga-tronics") (part "MHP200X92"))
    )
    (comp (ref "MTG74")
      (value "~")
      (footprint "MHP200X92")
      (description "MHP200X92")
      (fields (field (name "NOLOAD") "N/L"))
      (libsource (lib "Giga-tronics") (part "MHP200X92"))
    )
    (comp (ref "MTG76")
      (value "~")
      (footprint "MHP200X92")
      (description "MHP200X92")
      (fields (field (name "NOLOAD") "N/L"))
      (libsource (lib "Giga-tronics") (part "MHP200X92"))
    )
    (comp (ref "MTG77")
      (value "~")
      (footprint "MHP200X92")
      (description "MHP200X92")
      (fields (field (name "NOLOAD") "N/L"))
      (libsource (lib "Giga-tronics") (part "MHP200X92"))
    )
    (comp (ref "MTG80")
      (value "~")
      (footprint "MHP200X92")
      (description "MHP200X92")
      (fields (field (name "NOLOAD") "N/L"))
      (libsource (lib "Giga-tronics") (part "MHP200X92"))
    )
    (comp (ref "MTG81")
      (value "~")
      (footprint "MHP200X92")
      (description "MHP200X92")
      (fields (field (name "NOLOAD") "N/L"))
      (libsource (lib "Giga-tronics") (part "MHP200X92"))
    )
    (comp (ref "MTG82")
      (value "~")
      (footprint "MHP200X92")
      (description "MHP200X92")
      (fields (field (name "NOLOAD") "N/L"))
      (libsource (lib "Giga-tronics") (part "MHP200X92"))
    )
    (comp (ref "MTG83")
      (value "~")
      (footprint "MHP200X92")
      (description "MHP200X92")
      (fields (field (name "NOLOAD") "N/L"))
      (libsource (lib "Giga-tronics") (part "MHP200X92"))
    )
    (comp (ref "MTG84")
      (value "~")
      (footprint "MHP200X92")
      (description "MHP200X92")
      (fields (field (name "NOLOAD") "N/L"))
      (libsource (lib "Giga-tronics") (part "MHP200X92"))
    )
    (comp (ref "MTG85")
      (value "~")
      (footprint "MHP200X92")
      (description "MHP200X92")
      (fields (field (name "NOLOAD") "N/L"))
      (libsource (lib "Giga-tronics") (part "MHP200X92"))
    )
    (comp (ref "MTG88")
      (value "~")
      (footprint "MHP200X92")
      (description "MHP200X92")
      (fields (field (name "NOLOAD") "N/L"))
      (libsource (lib "Giga-tronics") (part "MHP200X92"))
    )
    (comp (ref "MTG94")
      (value "~")
      (footprint "MHP200X92")
      (description "MHP200X92")
      (fields (field (name "NOLOAD") "N/L"))
      (libsource (lib "Giga-tronics") (part "MHP200X92"))
    )
    (comp (ref "MTG95")
      (value "~")
      (footprint "MHP200X92")
      (description "MHP200X92")
      (fields (field (name "NOLOAD") "N/L"))
      (libsource (lib "Giga-tronics") (part "MHP200X92"))
    )
    (comp (ref "MTG97")
      (value "~")
      (footprint "MHP200X92")
      (description "MHP200X92")
      (fields (field (name "NOLOAD") "N/L"))
      (libsource (lib "Giga-tronics") (part "MHP200X92"))
    )
    (comp (ref "MTG98")
      (value "~")
      (footprint "MHP200X92")
      (description "MHP200X92")
      (fields (field (name "NOLOAD") "N/L"))
      (libsource (lib "Giga-tronics") (part "MHP200X92"))
    )
    (comp (ref "MTG99")
      (value "~")
      (footprint "MHP200X92")
      (description "MHP200X92")
      (fields (field (name "NOLOAD") "N/L"))
      (libsource (lib "Giga-tronics") (part "MHP200X92"))
    )
    (comp (ref "MTG100")
      (value "~")
      (footprint "MHP200X92")
      (description "MHP200X92")
      (fields (field (name "NOLOAD") "N/L"))
      (libsource (lib "Giga-tronics") (part "MHP200X92"))
    )
    (comp (ref "MTG101")
      (value "~")
      (footprint "MHP200X92")
      (description "MHP200X92")
      (fields (field (name "NOLOAD") "N/L"))
      (libsource (lib "Giga-tronics") (part "MHP200X92"))
    )
    (comp (ref "MTG102")
      (value "QMSS-CLAMP-ASSY")
      (footprint "QMSS-CLAMP")
      (description "connector retaining clip, KFH-440-12 stud, nut")
      (fields (field (name "NOLOAD") "N/L") (field (name "APPROVED") "*"))
      (libsource (lib "Giga-tronics") (part "QMSS-CLAMP-ASSY"))
    )
    (comp (ref "MTG110")
      (value "~")
      (footprint "MHP150X67")
      (description "MHP200X92")
      (fields (field (name "NOLOAD") "N/L"))
      (libsource (lib "Giga-tronics") (part "MHP150X67"))
    )
    (comp (ref "MTG111")
      (value "~")
      (footprint "MHP150X67")
      (description "MHP200X92")
      (fields (field (name "NOLOAD") "N/L"))
      (libsource (lib "Giga-tronics") (part "MHP150X67"))
    )
    (comp (ref "MTG112")
      (value "~")
      (footprint "MHP150X67")
      (description "MHP200X92")
      (fields (field (name "NOLOAD") "N/L"))
      (libsource (lib "Giga-tronics") (part "MHP150X67"))
    )
    (comp (ref "MTG113")
      (value "~")
      (footprint "MHP150X67")
      (description "MHP200X92")
      (fields (field (name "NOLOAD") "N/L"))
      (libsource (lib "Giga-tronics") (part "MHP150X67"))
    )
    (comp (ref "MTG201")
      (value "PLATED SLOT;380x190MIL")
      (footprint "PLATED_SLOT-380x190MIL")
      (fields (field (name "NOLOAD") "N/L"))
      (libsource (lib "Hydra_Ref_sch") (part "380x190MIL_SLOT"))
    )
    (comp (ref "PCA35117")
      (value "35117")
      (footprint "35117")
      (description "HYDRA A1-A3 BOARD PCA")
      (fields (field (name "NOLOAD") "N/L"))
      (libsource (lib "Hydra_Ref_sch") (part "35117"))
    )
  )
  (nets
    (net (code "162") (name "GND") (class "Default")
      (node (ref "MH10") (pin "MH") (pinfunction "1_MH") (pintype "passive"))
      (node (ref "MH11") (pin "MH") (pinfunction "1_MH") (pintype "passive"))
      (node (ref "MH12") (pin "MH") (pinfunction "1_MH") (pintype "passive"))
      (node (ref "MH13") (pin "MH") (pinfunction "1_MH") (pintype "passive"))
      (node (ref "MH14") (pin "MH") (pinfunction "1_MH") (pintype "passive"))
      (node (ref "MH15") (pin "MH") (pinfunction "1_MH") (pintype "passive"))
      (node (ref "MH16") (pin "MH") (pinfunction "1_MH") (pintype "passive"))
      (node (ref "MH17") (pin "MH") (pinfunction "1_MH") (pintype "passive"))
      (node (ref "MH18") (pin "MH") (pinfunction "1_MH") (pintype "passive"))
      (node (ref "MH19") (pin "MH") (pinfunction "1_MH") (pintype "passive"))
      (node (ref "MH2") (pin "MH") (pinfunction "1_MH") (pintype "passive"))
      (node (ref "MH5") (pin "MH") (pinfunction "1_MH") (pintype "passive"))
      (node (ref "MH6") (pin "MH") (pinfunction "1_MH") (pintype "passive"))
      (node (ref "MH7") (pin "MH") (pinfunction "1_MH") (pintype "passive"))
      (node (ref "MH9") (pin "MH") (pinfunction "1_MH") (pintype "passive"))
      (node (ref "MTG1") (pin "MH") (pintype "passive"))
      (node (ref "MTG10") (pin "MH") (pintype "passive"))
      (node (ref "MTG100") (pin "MH") (pintype "passive"))
      (node (ref "MTG101") (pin "MH") (pintype "passive"))
      (node (ref "MTG102") (pin "MH") (pinfunction "KFH-440-12_MH") (pintype "passive"))
      (node (ref "MTG11") (pin "MH") (pintype "passive"))
      (node (ref "MTG110") (pin "MH") (pintype "passive"))
      (node (ref "MTG111") (pin "MH") (pintype "passive"))
      (node (ref "MTG112") (pin "MH") (pintype "passive"))
      (node (ref "MTG113") (pin "MH") (pintype "passive"))
      (node (ref "MTG12") (pin "MH") (pintype "passive"))
      (node (ref "MTG13") (pin "MH") (pintype "passive"))
      (node (ref "MTG14") (pin "MH") (pintype "passive"))
      (node (ref "MTG15") (pin "MH") (pintype "passive"))
      (node (ref "MTG16") (pin "MH") (pintype "passive"))
      (node (ref "MTG17") (pin "MH") (pintype "passive"))
      (node (ref "MTG18") (pin "MH") (pintype "passive"))
      (node (ref "MTG19") (pin "MH") (pintype "passive"))
      (node (ref "MTG2") (pin "MH") (pintype "passive"))
      (node (ref "MTG20") (pin "MH") (pintype "passive"))
      (node (ref "MTG201") (pin "MH") (pinfunction "MH_MH") (pintype "passive"))
      (node (ref "MTG21") (pin "MH") (pintype "passive"))
      (node (ref "MTG22") (pin "MH") (pintype "passive"))
      (node (ref "MTG23") (pin "MH") (pintype "passive"))
      (node (ref "MTG24") (pin "MH") (pintype "passive"))
      (node (ref "MTG25") (pin "MH") (pintype "passive"))
      (node (ref "MTG26") (pin "MH") (pintype "passive"))
      (node (ref "MTG27") (pin "MH") (pintype "passive"))
      (node (ref "MTG28") (pin "MH") (pintype "passive"))
      (node (ref "MTG29") (pin "MH") (pintype "passive"))
      (node (ref "MTG3") (pin "MH") (pintype "passive"))
      (node (ref "MTG30") (pin "MH") (pintype "passive"))
      (node (ref "MTG31") (pin "MH") (pintype "passive"))
      (node (ref "MTG34") (pin "MH") (pintype "passive"))
      (node (ref "MTG38") (pin "MH") (pintype "passive"))
      (node (ref "MTG39") (pin "MH") (pintype "passive"))
      (node (ref "MTG4") (pin "MH") (pintype "passive"))
      (node (ref "MTG40") (pin "MH") (pintype "passive"))
      (node (ref "MTG41") (pin "MH") (pintype "passive"))
      (node (ref "MTG42") (pin "MH") (pintype "passive"))
      (node (ref "MTG43") (pin "MH") (pintype "passive"))
      (node (ref "MTG44") (pin "MH") (pintype "passive"))
      (node (ref "MTG46") (pin "MH") (pintype "passive"))
      (node (ref "MTG47") (pin "MH") (pintype "passive"))
      (node (ref "MTG48") (pin "MH") (pintype "passive"))
      (node (ref "MTG49") (pin "MH") (pintype "passive"))
      (node (ref "MTG50") (pin "MH") (pintype "passive"))
      (node (ref "MTG51") (pin "MH") (pintype "passive"))
      (node (ref "MTG52") (pin "MH") (pintype "passive"))
      (node (ref "MTG53") (pin "MH") (pintype "passive"))
      (node (ref "MTG54") (pin "MH") (pintype "passive"))
      (node (ref "MTG55") (pin "MH") (pintype "passive"))
      (node (ref "MTG56") (pin "MH") (pintype "passive"))
      (node (ref "MTG57") (pin "MH") (pintype "passive"))
      (node (ref "MTG58") (pin "MH") (pintype "passive"))
      (node (ref "MTG59") (pin "MH") (pintype "passive"))
      (node (ref "MTG6") (pin "MH") (pintype "passive"))
      (node (ref "MTG60") (pin "MH") (pintype "passive"))
      (node (ref "MTG61") (pin "MH") (pintype "passive"))
      (node (ref "MTG67") (pin "MH") (pintype "passive"))
      (node (ref "MTG68") (pin "MH") (pintype "passive"))
      (node (ref "MTG69") (pin "MH") (pintype "passive"))
      (node (ref "MTG7") (pin "MH") (pintype "passive"))
      (node (ref "MTG70") (pin "MH") (pintype "passive"))
      (node (ref "MTG71") (pin "MH") (pintype "passive"))
      (node (ref "MTG72") (pin "MH") (pintype "passive"))
      (node (ref "MTG74") (pin "MH") (pintype "passive"))
      (node (ref "MTG76") (pin "MH") (pintype "passive"))
      (node (ref "MTG77") (pin "MH") (pintype "passive"))
      (node (ref "MTG8") (pin "MH") (pintype "passive"))
      (node (ref "MTG80") (pin "MH") (pintype "passive"))
      (node (ref "MTG81") (pin "MH") (pintype "passive"))
      (node (ref "MTG82") (pin "MH") (pintype "passive"))
      (node (ref "MTG83") (pin "MH") (pintype "passive"))
      (node (ref "MTG84") (pin "MH") (pintype "passive"))
      (node (ref "MTG85") (pin "MH") (pintype "passive"))
      (node (ref "MTG88") (pin "MH") (pintype "passive"))
      (node (ref "MTG94") (pin "MH") (pintype "passive"))
      (node (ref "MTG95") (pin "MH") (pintype "passive"))
      (node (ref "MTG97") (pin "MH") (pintype "passive"))
      (node (ref "MTG98") (pin "MH") (pintype "passive"))
      (node (ref "MTG99") (pin "MH") (pintype "passive"))
      (node (ref "PCA35117") (pin "MH1") (pinfunction "MH1_MH1") (pintype "passive"))
      (node (ref "PCA35117") (pin "MH2") (pinfunction "MH2_MH2") (pintype "passive"))
    )
    (net (code "163") (name "unconnected-(FUD1-Pad1)") (class "Default")
      (node (ref "FUD1") (pin "1") (pintype "passive"))
    )
    (net (code "164") (name "unconnected-(FUD2-Pad1)") (class "Default")
      (node (ref "FUD2") (pin "1") (pintype "passive"))
    )
    (net (code "165") (name "unconnected-(FUD3-Pad1)") (class "Default")
      (node (ref "FUD3") (pin "1") (pintype "passive"))
    )
    (net (code "166") (name "unconnected-(FUD4-Pad1)") (class "Default")
      (node (ref "FUD4") (pin "1") (pintype "passive"))
    )
    (net (code "167") (name "unconnected-(FUD5-Pad1)") (class "Default")
      (node (ref "FUD5") (pin "1") (pintype "passive"))
    )
    (net (code "168") (name "unconnected-(FUD6-Pad1)") (class "Default")
      (node (ref "FUD6") (pin "1") (pintype "passive"))
    )
  )
)
